# PowerConnector.net
KiCad netlist of a schematic drawn in Altium Designer
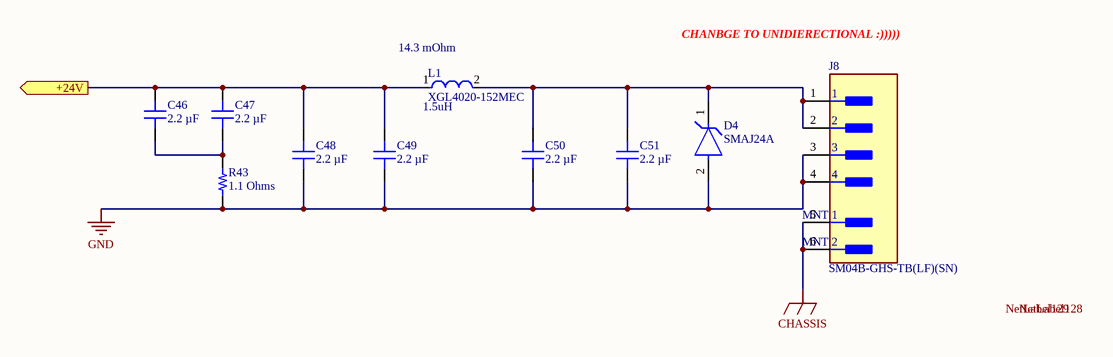
[diagram p0: PowerConnector.SchDoc]

(export (version "E")
  (design (tool "Eeschema 10.0.6"))
  (components
    (comp (ref "C46")
      (value "2.2 µF")
      (footprint "CAP 0805_2012")
      (description "CAP CER 2.2UF 50V X5R 0805")
      (fields
        (field (name "PART NUMBER") "CGA4J3X5R1H225K125AB")
        (field (name "CAPACITANCE") "2.2 µF")
        (field (name "MANUFACTURER") "TDK Corporation")
      )
      (libsource (lib "Celestial Altium Library - altium_library") (part "Capacitor"))
    )
    (comp (ref "C47")
      (value "2.2 µF")
      (footprint "CAP 0805_2012")
      (description "CAP CER 2.2UF 50V X5R 0805")
      (fields
        (field (name "PART NUMBER") "CGA4J3X5R1H225K125AB")
        (field (name "CAPACITANCE") "2.2 µF")
        (field (name "MANUFACTURER") "TDK Corporation")
      )
      (libsource (lib "Celestial Altium Library - altium_library") (part "Capacitor"))
    )
    (comp (ref "C48")
      (value "2.2 µF")
      (footprint "CAP 0805_2012")
      (description "CAP CER 2.2UF 50V X5R 0805")
      (fields
        (field (name "PART NUMBER") "CGA4J3X5R1H225K125AB")
        (field (name "CAPACITANCE") "2.2 µF")
        (field (name "MANUFACTURER") "TDK Corporation")
      )
      (libsource (lib "Celestial Altium Library - altium_library") (part "Capacitor"))
    )
    (comp (ref "C49")
      (value "2.2 µF")
      (footprint "CAP 0805_2012")
      (description "CAP CER 2.2UF 50V X5R 0805")
      (fields
        (field (name "PART NUMBER") "CGA4J3X5R1H225K125AB")
        (field (name "CAPACITANCE") "2.2 µF")
        (field (name "MANUFACTURER") "TDK Corporation")
      )
      (libsource (lib "Celestial Altium Library - altium_library") (part "Capacitor"))
    )
    (comp (ref "C50")
      (value "2.2 µF")
      (footprint "CAP 0805_2012")
      (description "CAP CER 2.2UF 50V X5R 0805")
      (fields
        (field (name "PART NUMBER") "CGA4J3X5R1H225K125AB")
        (field (name "CAPACITANCE") "2.2 µF")
        (field (name "MANUFACTURER") "TDK Corporation")
      )
      (libsource (lib "Celestial Altium Library - altium_library") (part "Capacitor"))
    )
    (comp (ref "C51")
      (value "2.2 µF")
      (footprint "CAP 0805_2012")
      (description "CAP CER 2.2UF 50V X5R 0805")
      (fields
        (field (name "PART NUMBER") "CGA4J3X5R1H225K125AB")
        (field (name "CAPACITANCE") "2.2 µF")
        (field (name "MANUFACTURER") "TDK Corporation")
      )
      (libsource (lib "Celestial Altium Library - altium_library") (part "Capacitor"))
    )
    (comp (ref "D4")
      (value "SMAJ24A")
      (footprint "FP-SMAJ-MFG")
      (description "TVS DIODE 24V 38.9V DO214AC")
      (fields
        (field (name "OCTOPART") "https://octopart.com/smaj24a-littelfuse-350003")
        (field (name "MANUFACTURER") "Littelfuse Inc")
      )
      (libsource (lib "Altium Content Vault") (part "f813f71cba58e380607f5dd3caf9714"))
    )
    (comp (ref "J8")
      (value "SM04B-GHS-TB(LF)(SN)")
      (footprint "FP-SM04B-GHS-TB_LF_SN-MFG")
      (description "CONN HEADER SMD R/A 4POS 1.25MM")
      (libsource (lib "Altium Content Vault") (part "f4320a1371cd6270e33bce1916c33c0"))
    )
    (comp (ref "L1")
      (value "XGL4020-152MEC")
      (footprint "FP-XGL4020-MFG")
      (description "Shielded Power Inductors")
      (fields
        (field (name "MANUFACTURER") "Coilcraft")
        (field (name "ALTIUM_VALUE") "1.5uH")
        (field (name "TOLERANCE") "20%")
      )
      (libsource (lib "Altium Content Vault") (part "725321dda6339637d4d059423bc1c3c"))
    )
    (comp (ref "R43")
      (value "1.1 Ohms")
      (footprint "RES 0603_1608")
      (description "RES 1.1 OHM 1% 1/5W 0603")
      (fields
        (field (name "PART NUMBER") "SR731JRTTD1R10F")
        (field (name "MANUFACTURER") "KOA Speer Electronics, Inc.")
      )
      (libsource (lib "Celestial Altium Library - altium_library") (part "Resistor"))
    )
  )
  (nets
    (net (code "1") (name "/+24V") (class "Default")
      (node (ref "C46") (pin "2") (pinfunction "2_2") (pintype "passive"))
      (node (ref "C47") (pin "2") (pinfunction "2_2") (pintype "passive"))
      (node (ref "C48") (pin "2") (pinfunction "2_2") (pintype "passive"))
      (node (ref "C49") (pin "2") (pinfunction "2_2") (pintype "passive"))
      (node (ref "L1") (pin "1") (pinfunction "1_1") (pintype "passive"))
    )
    (net (code "4") (name "CHASSIS") (class "Default")
      (node (ref "J8") (pin "5") (pinfunction "MNT_1_5") (pintype "passive"))
      (node (ref "J8") (pin "6") (pinfunction "MNT_2_6") (pintype "passive"))
    )
    (net (code "5") (name "GND") (class "Default")
      (node (ref "C48") (pin "1") (pinfunction "1_1") (pintype "passive"))
      (node (ref "C49") (pin "1") (pinfunction "1_1") (pintype "passive"))
      (node (ref "C50") (pin "1") (pinfunction "1_1") (pintype "passive"))
      (node (ref "C51") (pin "1") (pinfunction "1_1") (pintype "passive"))
      (node (ref "D4") (pin "2") (pinfunction "A_2") (pintype "passive"))
      (node (ref "J8") (pin "3") (pinfunction "3_3") (pintype "passive"))
      (node (ref "J8") (pin "4") (pinfunction "4_4") (pintype "passive"))
      (node (ref "R43") (pin "1") (pinfunction "1_1") (pintype "passive"))
    )
    (net (code "6") (name "Net-(C46-Pad1)") (class "Default")
      (node (ref "C46") (pin "1") (pinfunction "1_1") (pintype "passive"))
      (node (ref "C47") (pin "1") (pinfunction "1_1") (pintype "passive"))
      (node (ref "R43") (pin "2") (pinfunction "2_2") (pintype "passive"))
    )
    (net (code "7") (name "Net-(D4-C)") (class "Default")
      (node (ref "C50") (pin "2") (pinfunction "2_2") (pintype "passive"))
      (node (ref "C51") (pin "2") (pinfunction "2_2") (pintype "passive"))
      (node (ref "D4") (pin "1") (pinfunction "C_1") (pintype "passive"))
      (node (ref "J8") (pin "1") (pinfunction "1_1") (pintype "passive"))
      (node (ref "J8") (pin "2") (pinfunction "2_2") (pintype "passive"))
      (node (ref "L1") (pin "2") (pinfunction "2_2") (pintype "passive"))
    )
  )
)
